# AnalExtend.net
KiCad netlist of a schematic drawn in Altium Designer
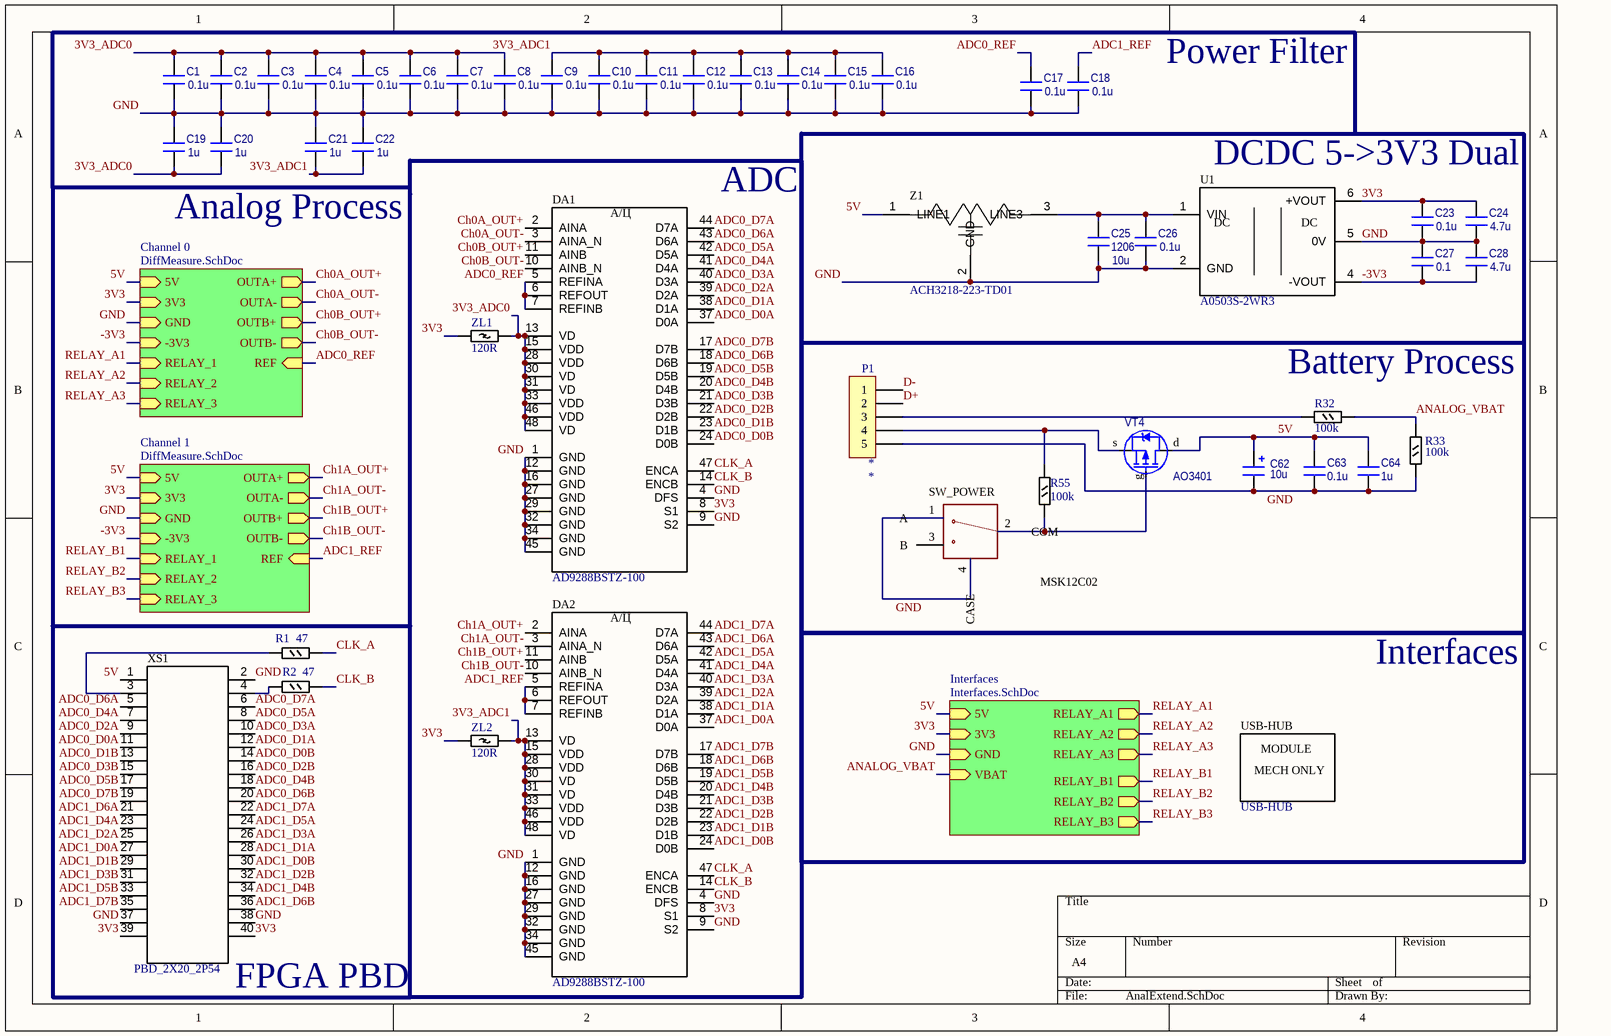
[diagram p0: AnalExtend.SchDoc]

(export (version "E")
  (design (tool "Eeschema 10.0.6"))
  (components
    (comp (ref "C1")
      (value "0.1u")
      (footprint "CAPC2012(0805)N")
      (fields (field (name "PART NUMBER") "CAPC2012(0805)"))
      (libsource (lib "SssAccesDatbase") (part "Capacitor generic"))
    )
    (comp (ref "C2")
      (value "0.1u")
      (footprint "CAPC2012(0805)N")
      (fields (field (name "PART NUMBER") "CAPC2012(0805)"))
      (libsource (lib "SssAccesDatbase") (part "Capacitor generic"))
    )
    (comp (ref "C3")
      (value "0.1u")
      (footprint "CAPC2012(0805)N")
      (fields (field (name "PART NUMBER") "CAPC2012(0805)"))
      (libsource (lib "SssAccesDatbase") (part "Capacitor generic"))
    )
    (comp (ref "C4")
      (value "0.1u")
      (footprint "CAPC2012(0805)N")
      (fields (field (name "PART NUMBER") "CAPC2012(0805)"))
      (libsource (lib "SssAccesDatbase") (part "Capacitor generic"))
    )
    (comp (ref "C5")
      (value "0.1u")
      (footprint "CAPC2012(0805)N")
      (fields (field (name "PART NUMBER") "CAPC2012(0805)"))
      (libsource (lib "SssAccesDatbase") (part "Capacitor generic"))
    )
    (comp (ref "C6")
      (value "0.1u")
      (footprint "CAPC2012(0805)N")
      (fields (field (name "PART NUMBER") "CAPC2012(0805)"))
      (libsource (lib "SssAccesDatbase") (part "Capacitor generic"))
    )
    (comp (ref "C7")
      (value "0.1u")
      (footprint "CAPC2012(0805)N")
      (fields (field (name "PART NUMBER") "CAPC2012(0805)"))
      (libsource (lib "SssAccesDatbase") (part "Capacitor generic"))
    )
    (comp (ref "C8")
      (value "0.1u")
      (footprint "CAPC2012(0805)N")
      (fields (field (name "PART NUMBER") "CAPC2012(0805)"))
      (libsource (lib "SssAccesDatbase") (part "Capacitor generic"))
    )
    (comp (ref "C9")
      (value "0.1u")
      (footprint "CAPC2012(0805)N")
      (fields (field (name "PART NUMBER") "CAPC2012(0805)"))
      (libsource (lib "SssAccesDatbase") (part "Capacitor generic"))
    )
    (comp (ref "C10")
      (value "0.1u")
      (footprint "CAPC2012(0805)N")
      (fields (field (name "PART NUMBER") "CAPC2012(0805)"))
      (libsource (lib "SssAccesDatbase") (part "Capacitor generic"))
    )
    (comp (ref "C11")
      (value "0.1u")
      (footprint "CAPC2012(0805)N")
      (fields (field (name "PART NUMBER") "CAPC2012(0805)"))
      (libsource (lib "SssAccesDatbase") (part "Capacitor generic"))
    )
    (comp (ref "C12")
      (value "0.1u")
      (footprint "CAPC2012(0805)N")
      (fields (field (name "PART NUMBER") "CAPC2012(0805)"))
      (libsource (lib "SssAccesDatbase") (part "Capacitor generic"))
    )
    (comp (ref "C13")
      (value "0.1u")
      (footprint "CAPC2012(0805)N")
      (fields (field (name "PART NUMBER") "CAPC2012(0805)"))
      (libsource (lib "SssAccesDatbase") (part "Capacitor generic"))
    )
    (comp (ref "C14")
      (value "0.1u")
      (footprint "CAPC2012(0805)N")
      (fields (field (name "PART NUMBER") "CAPC2012(0805)"))
      (libsource (lib "SssAccesDatbase") (part "Capacitor generic"))
    )
    (comp (ref "C15")
      (value "0.1u")
      (footprint "CAPC2012(0805)N")
      (fields (field (name "PART NUMBER") "CAPC2012(0805)"))
      (libsource (lib "SssAccesDatbase") (part "Capacitor generic"))
    )
    (comp (ref "C16")
      (value "0.1u")
      (footprint "CAPC2012(0805)N")
      (fields (field (name "PART NUMBER") "CAPC2012(0805)"))
      (libsource (lib "SssAccesDatbase") (part "Capacitor generic"))
    )
    (comp (ref "C17")
      (value "0.1u")
      (footprint "CAPC2012(0805)N")
      (fields (field (name "PART NUMBER") "CAPC2012(0805)"))
      (libsource (lib "SssAccesDatbase") (part "Capacitor generic"))
    )
    (comp (ref "C18")
      (value "0.1u")
      (footprint "CAPC2012(0805)N")
      (fields (field (name "PART NUMBER") "CAPC2012(0805)"))
      (libsource (lib "SssAccesDatbase") (part "Capacitor generic"))
    )
    (comp (ref "C19")
      (value "1u")
      (footprint "CAPC2012(0805)N")
      (fields (field (name "PART NUMBER") "CAPC2012(0805)"))
      (libsource (lib "SssAccesDatbase") (part "Capacitor generic"))
    )
    (comp (ref "C20")
      (value "1u")
      (footprint "CAPC2012(0805)N")
      (fields (field (name "PART NUMBER") "CAPC2012(0805)"))
      (libsource (lib "SssAccesDatbase") (part "Capacitor generic"))
    )
    (comp (ref "C21")
      (value "1u")
      (footprint "CAPC2012(0805)N")
      (fields (field (name "PART NUMBER") "CAPC2012(0805)"))
      (libsource (lib "SssAccesDatbase") (part "Capacitor generic"))
    )
    (comp (ref "C22")
      (value "1u")
      (footprint "CAPC2012(0805)N")
      (fields (field (name "PART NUMBER") "CAPC2012(0805)"))
      (libsource (lib "SssAccesDatbase") (part "Capacitor generic"))
    )
    (comp (ref "C23")
      (value "0.1u")
      (footprint "CAPC2012(0805)N")
      (fields (field (name "PART NUMBER") "CAPC2012(0805)"))
      (libsource (lib "SssAccesDatbase") (part "Capacitor generic"))
    )
    (comp (ref "C24")
      (value "4.7u")
      (footprint "CAPC2012(0805)N")
      (fields (field (name "PART NUMBER") "CAPC2012(0805)"))
      (libsource (lib "SssAccesDatbase") (part "Capacitor generic"))
    )
    (comp (ref "C25")
      (value "10u")
      (footprint "CAP_CER_1206")
      (description "Cap Cer MLCC SMD 50V 2700p C0G NP0 1206 2%")
      (fields
        (field (name "PACKAGE") "1206")
        (field (name "PART NUMBER") "12065A272GAT2A")
        (field (name "MOUSER PART NUMBER") "581-12065A272G")
      )
      (libsource (lib "SssAccesDatbase") (part "Capacitor generic"))
    )
    (comp (ref "C26")
      (value "0.1u")
      (footprint "CAPC2012(0805)N")
      (fields (field (name "PART NUMBER") "CAPC2012(0805)"))
      (libsource (lib "SssAccesDatbase") (part "Capacitor generic"))
    )
    (comp (ref "C27")
      (value "0.1")
      (footprint "CAPC2012(0805)N")
      (fields (field (name "PART NUMBER") "CAPC2012(0805)"))
      (libsource (lib "SssAccesDatbase") (part "Capacitor generic"))
    )
    (comp (ref "C28")
      (value "4.7u")
      (footprint "CAPC2012(0805)N")
      (fields (field (name "PART NUMBER") "CAPC2012(0805)"))
      (libsource (lib "SssAccesDatbase") (part "Capacitor generic"))
    )
    (comp (ref "C62")
      (value "10u")
      (footprint "CAPMP3528X210N")
      (description "Tantalum Capacitors - Solid SMD 35V 1uF 10%")
      (fields (field (name "PART NUMBER") "TAJB105K035SNJ") (field (name "MPN") "581-TAJB105K035S"))
      (libsource (lib "SssAccesDatbase") (part "Capacitor generic polar"))
    )
    (comp (ref "C63")
      (value "0.1u")
      (footprint "CAPC2012(0805)N")
      (fields (field (name "PACKAGE") "0.1u") (field (name "PART NUMBER") "CAPC2012(0805)"))
      (libsource (lib "SssAccesDatbase") (part "Capacitor generic"))
    )
    (comp (ref "C64")
      (value "1u")
      (footprint "CAPC2012(0805)N")
      (fields (field (name "PACKAGE") "1u") (field (name "PART NUMBER") "CAPC2012(0805)"))
      (libsource (lib "SssAccesDatbase") (part "Capacitor generic"))
    )
    (comp (ref "DA1")
      (value "AD9288BSTZ-100")
      (footprint "AD9288BSTZ-100_LQFP48")
      (description "Analog Devices dual 8-bit ADC, 100 MSPS, LQFP-48 ST-48")
      (libsource (lib "Oscill") (part "AD9288BSTZ-100"))
    )
    (comp (ref "DA2")
      (value "AD9288BSTZ-100")
      (footprint "AD9288BSTZ-100_LQFP48")
      (description "Analog Devices dual 8-bit ADC, 100 MSPS, LQFP-48 ST-48")
      (libsource (lib "Oscill") (part "AD9288BSTZ-100"))
    )
    (comp (ref "P1")
      (value "P_HEADER_1x5")
      (footprint "P_HEADER_1x5_2.54_ANGLE")
      (description "Pin Header")
      (fields (field (name "SCH_FOOTPRINT") "*") (field (name "ALTIUM_VALUE") "*"))
      (libsource (lib "P_HEADER_1x5") (part "P_HEADER_1x5"))
    )
    (comp (ref "R1")
      (value "47")
      (footprint "RESC2012(0805)N")
      (fields (field (name "PART NUMBER") "RESC2012(0805)"))
      (libsource (lib "SssAccesDatbase") (part "Resistor 0,125W"))
    )
    (comp (ref "R2")
      (value "47")
      (footprint "RESC2012(0805)N")
      (fields (field (name "PART NUMBER") "RESC2012(0805)"))
      (libsource (lib "SssAccesDatbase") (part "Resistor 0,125W"))
    )
    (comp (ref "R32")
      (value "100k")
      (footprint "RESC2012(0805)N")
      (fields (field (name "PART NUMBER") "RESC2012(0805)"))
      (libsource (lib "SssAccesDatbase") (part "Resistor 0,125W"))
    )
    (comp (ref "R33")
      (value "100k")
      (footprint "RESC2012(0805)N")
      (fields (field (name "PART NUMBER") "RESC2012(0805)"))
      (libsource (lib "") (part "Resistor 0,125W_2"))
    )
    (comp (ref "R55")
      (value "100k")
      (footprint "RESC2012(0805)N")
      (fields (field (name "PART NUMBER") "RESC2012(0805)"))
      (libsource (lib "") (part "Resistor 0,125W_1"))
    )
    (comp (ref "SW_POWER")
      (value "MSK12C02")
      (footprint "MSK12C02")
      (description "Shou Han MSK12C02 miniature SMD SPDT slide switch, ON-ON, 12 VDC 50 mA; four case tabs are pin 4")
      (fields (field (name "MANUFACTURER") "SHOU HAN") (field (name "LCSC PART NUMBER") "C431540"))
      (libsource (lib "MSK12C02") (part "MSK12C02"))
    )
    (comp (ref "U1")
      (value "A0503S-2WR3")
      (footprint "A0503S-2WR3_SIP5")
      (description "YLPTEC 2 W isolated DC/DC, 5 V input, +/-3.3 V dual output")
      (libsource (lib "Oscill") (part "A0503S-2WR3"))
    )
    (comp (ref "USB-HUB")
      (value "USB-HUB")
      (footprint "Oscill:MINGWU_29P3X18P9_MECH")
      (description "Mechanical-only Mingwudianzi module; no electrical pins")
      (libsource (lib "Oscill") (part "MINGWU_29P3X18P9_MECH"))
    )
    (comp (ref "VT4")
      (value "AO3401")
      (footprint "SOT23-3N")
      (description "MOSFET 30V P-Channel Enhancement Mode MOSFET-ESD Protected")
      (fields
        (field (name "PART NUMBER") "PJA3433_R1_00001")
        (field (name "DIGI-KEY PART NUMBER") "3757-PJA3433_R1_00001CT-ND")
      )
      (libsource (lib "SssAccesDatbase") (part "TRANS-P-Channel-GSD"))
    )
    (comp (ref "XS1")
      (value "PBD_2X20_2P54")
      (footprint "PBD_2X20_2P54_THT")
      (description "PBD-40 vertical 2x20 2.54 mm female through-hole socket")
      (libsource (lib "Oscill") (part "PBD_2X20_2P54"))
    )
    (comp (ref "Z1")
      (value "ACH3218-223-TD01")
      (footprint "ACH3218_3TERM_FILTER")
      (description "TDK 22 nF three-terminal T-type EMI filter, 20 V, 1.5 A")
      (libsource (lib "Oscill") (part "ACH3218-223-TD01"))
    )
    (comp (ref "ZL1")
      (value "120R")
      (footprint "INDC1608(0603)N")
      (description "ferite bead")
      (fields
        (field (name "PART NUMBER") "Ferite1608(0603)")
        (field (name "MANUFACTURER PART NUMBER") "BLM15PX471SN1D")
      )
      (libsource (lib "SssAccesDatbase") (part "ZL"))
    )
    (comp (ref "ZL2")
      (value "120R")
      (footprint "INDC1608(0603)N")
      (description "ferite bead")
      (fields
        (field (name "PART NUMBER") "Ferite1608(0603)")
        (field (name "MANUFACTURER PART NUMBER") "BLM15PX471SN1D")
      )
      (libsource (lib "SssAccesDatbase") (part "ZL"))
    )
  )
  (nets
    (net (code "1") (name "/-3V3") (class "Default")
      (node (ref "C27") (pin "2") (pinfunction "2_2") (pintype "passive"))
      (node (ref "C28") (pin "2") (pinfunction "2_2") (pintype "passive"))
      (node (ref "U1") (pin "4") (pinfunction "-VOUT_4") (pintype "passive"))
    )
    (net (code "2") (name "/3V3") (class "Default")
      (node (ref "C23") (pin "1") (pinfunction "1_1") (pintype "passive"))
      (node (ref "C24") (pin "1") (pinfunction "1_1") (pintype "passive"))
      (node (ref "DA1") (pin "8") (pinfunction "S1_8") (pintype "passive"))
      (node (ref "DA2") (pin "8") (pinfunction "S1_8") (pintype "passive"))
      (node (ref "U1") (pin "6") (pinfunction "+VOUT_6") (pintype "passive"))
      (node (ref "XS1") (pin "39") (pintype "passive"))
      (node (ref "XS1") (pin "40") (pintype "passive"))
      (node (ref "ZL1") (pin "1") (pinfunction "1_1") (pintype "passive"))
      (node (ref "ZL2") (pin "1") (pinfunction "1_1") (pintype "passive"))
    )
    (net (code "3") (name "/3V3_ADC0") (class "Default")
      (node (ref "C1") (pin "1") (pinfunction "1_1") (pintype "passive"))
      (node (ref "C19") (pin "2") (pinfunction "2_2") (pintype "passive"))
      (node (ref "C2") (pin "1") (pinfunction "1_1") (pintype "passive"))
      (node (ref "C20") (pin "2") (pinfunction "2_2") (pintype "passive"))
      (node (ref "C3") (pin "1") (pinfunction "1_1") (pintype "passive"))
      (node (ref "C4") (pin "1") (pinfunction "1_1") (pintype "passive"))
      (node (ref "C5") (pin "1") (pinfunction "1_1") (pintype "passive"))
      (node (ref "C6") (pin "1") (pinfunction "1_1") (pintype "passive"))
      (node (ref "C7") (pin "1") (pinfunction "1_1") (pintype "passive"))
      (node (ref "C8") (pin "1") (pinfunction "1_1") (pintype "passive"))
      (node (ref "DA1") (pin "13") (pinfunction "VD_13") (pintype "passive"))
      (node (ref "DA1") (pin "15") (pinfunction "VDD_15") (pintype "passive"))
      (node (ref "DA1") (pin "28") (pinfunction "VDD_28") (pintype "passive"))
      (node (ref "DA1") (pin "30") (pinfunction "VD_30") (pintype "passive"))
      (node (ref "DA1") (pin "31") (pinfunction "VD_31") (pintype "passive"))
      (node (ref "DA1") (pin "33") (pinfunction "VDD_33") (pintype "passive"))
      (node (ref "DA1") (pin "46") (pinfunction "VDD_46") (pintype "passive"))
      (node (ref "DA1") (pin "48") (pinfunction "VD_48") (pintype "passive"))
      (node (ref "ZL1") (pin "2") (pinfunction "2_2") (pintype "passive"))
    )
    (net (code "4") (name "/3V3_ADC1") (class "Default")
      (node (ref "C10") (pin "1") (pinfunction "1_1") (pintype "passive"))
      (node (ref "C11") (pin "1") (pinfunction "1_1") (pintype "passive"))
      (node (ref "C12") (pin "1") (pinfunction "1_1") (pintype "passive"))
      (node (ref "C13") (pin "1") (pinfunction "1_1") (pintype "passive"))
      (node (ref "C14") (pin "1") (pinfunction "1_1") (pintype "passive"))
      (node (ref "C15") (pin "1") (pinfunction "1_1") (pintype "passive"))
      (node (ref "C16") (pin "1") (pinfunction "1_1") (pintype "passive"))
      (node (ref "C21") (pin "2") (pinfunction "2_2") (pintype "passive"))
      (node (ref "C22") (pin "2") (pinfunction "2_2") (pintype "passive"))
      (node (ref "C9") (pin "1") (pinfunction "1_1") (pintype "passive"))
      (node (ref "DA2") (pin "13") (pinfunction "VD_13") (pintype "passive"))
      (node (ref "DA2") (pin "15") (pinfunction "VDD_15") (pintype "passive"))
      (node (ref "DA2") (pin "28") (pinfunction "VDD_28") (pintype "passive"))
      (node (ref "DA2") (pin "30") (pinfunction "VD_30") (pintype "passive"))
      (node (ref "DA2") (pin "31") (pinfunction "VD_31") (pintype "passive"))
      (node (ref "DA2") (pin "33") (pinfunction "VDD_33") (pintype "passive"))
      (node (ref "DA2") (pin "46") (pinfunction "VDD_46") (pintype "passive"))
      (node (ref "DA2") (pin "48") (pinfunction "VD_48") (pintype "passive"))
      (node (ref "ZL2") (pin "2") (pinfunction "2_2") (pintype "passive"))
    )
    (net (code "5") (name "/5V") (class "Default")
      (node (ref "C62") (pin "1") (pinfunction "1_1") (pintype "passive"))
      (node (ref "C63") (pin "1") (pinfunction "1_1") (pintype "passive"))
      (node (ref "C64") (pin "1") (pinfunction "1_1") (pintype "passive"))
      (node (ref "VT4") (pin "d") (pinfunction "d_d") (pintype "passive"))
      (node (ref "XS1") (pin "1") (pintype "passive"))
      (node (ref "Z1") (pin "1") (pinfunction "LINE1_1") (pintype "passive"))
    )
    (net (code "6") (name "/ADC0_D0A") (class "Default")
      (node (ref "DA1") (pin "37") (pinfunction "D0A_37") (pintype "passive"))
      (node (ref "XS1") (pin "11") (pintype "passive"))
    )
    (net (code "7") (name "/ADC0_D0B") (class "Default")
      (node (ref "DA1") (pin "24") (pinfunction "D0B_24") (pintype "passive"))
      (node (ref "XS1") (pin "14") (pintype "passive"))
    )
    (net (code "8") (name "/ADC0_D1A") (class "Default")
      (node (ref "DA1") (pin "38") (pinfunction "D1A_38") (pintype "passive"))
      (node (ref "XS1") (pin "12") (pintype "passive"))
    )
    (net (code "9") (name "/ADC0_D1B") (class "Default")
      (node (ref "DA1") (pin "23") (pinfunction "D1B_23") (pintype "passive"))
      (node (ref "XS1") (pin "13") (pintype "passive"))
    )
    (net (code "10") (name "/ADC0_D2A") (class "Default")
      (node (ref "DA1") (pin "39") (pinfunction "D2A_39") (pintype "passive"))
      (node (ref "XS1") (pin "9") (pintype "passive"))
    )
    (net (code "11") (name "/ADC0_D2B") (class "Default")
      (node (ref "DA1") (pin "22") (pinfunction "D2B_22") (pintype "passive"))
      (node (ref "XS1") (pin "16") (pintype "passive"))
    )
    (net (code "12") (name "/ADC0_D3A") (class "Default")
      (node (ref "DA1") (pin "40") (pinfunction "D3A_40") (pintype "passive"))
      (node (ref "XS1") (pin "10") (pintype "passive"))
    )
    (net (code "13") (name "/ADC0_D3B") (class "Default")
      (node (ref "DA1") (pin "21") (pinfunction "D3B_21") (pintype "passive"))
      (node (ref "XS1") (pin "15") (pintype "passive"))
    )
    (net (code "14") (name "/ADC0_D4A") (class "Default")
      (node (ref "DA1") (pin "41") (pinfunction "D4A_41") (pintype "passive"))
      (node (ref "XS1") (pin "7") (pintype "passive"))
    )
    (net (code "15") (name "/ADC0_D4B") (class "Default")
      (node (ref "DA1") (pin "20") (pinfunction "D4B_20") (pintype "passive"))
      (node (ref "XS1") (pin "18") (pintype "passive"))
    )
    (net (code "16") (name "/ADC0_D5A") (class "Default")
      (node (ref "DA1") (pin "42") (pinfunction "D5A_42") (pintype "passive"))
      (node (ref "XS1") (pin "8") (pintype "passive"))
    )
    (net (code "17") (name "/ADC0_D5B") (class "Default")
      (node (ref "DA1") (pin "19") (pinfunction "D5B_19") (pintype "passive"))
      (node (ref "XS1") (pin "17") (pintype "passive"))
    )
    (net (code "18") (name "/ADC0_D6A") (class "Default")
      (node (ref "DA1") (pin "43") (pinfunction "D6A_43") (pintype "passive"))
      (node (ref "XS1") (pin "5") (pintype "passive"))
    )
    (net (code "19") (name "/ADC0_D6B") (class "Default")
      (node (ref "DA1") (pin "18") (pinfunction "D6B_18") (pintype "passive"))
      (node (ref "XS1") (pin "20") (pintype "passive"))
    )
    (net (code "20") (name "/ADC0_D7A") (class "Default")
      (node (ref "DA1") (pin "44") (pinfunction "D7A_44") (pintype "passive"))
      (node (ref "XS1") (pin "6") (pintype "passive"))
    )
    (net (code "21") (name "/ADC0_D7B") (class "Default")
      (node (ref "DA1") (pin "17") (pinfunction "D7B_17") (pintype "passive"))
      (node (ref "XS1") (pin "19") (pintype "passive"))
    )
    (net (code "22") (name "/ADC0_REF") (class "Default")
      (node (ref "C17") (pin "1") (pinfunction "1_1") (pintype "passive"))
      (node (ref "DA1") (pin "5") (pinfunction "REFINA_5") (pintype "passive"))
      (node (ref "DA1") (pin "6") (pinfunction "REFOUT_6") (pintype "passive"))
      (node (ref "DA1") (pin "7") (pinfunction "REFINB_7") (pintype "passive"))
    )
    (net (code "23") (name "/ADC1_D0A") (class "Default")
      (node (ref "DA2") (pin "37") (pinfunction "D0A_37") (pintype "passive"))
      (node (ref "XS1") (pin "27") (pintype "passive"))
    )
    (net (code "24") (name "/ADC1_D0B") (class "Default")
      (node (ref "DA2") (pin "24") (pinfunction "D0B_24") (pintype "passive"))
      (node (ref "XS1") (pin "30") (pintype "passive"))
    )
    (net (code "25") (name "/ADC1_D1A") (class "Default")
      (node (ref "DA2") (pin "38") (pinfunction "D1A_38") (pintype "passive"))
      (node (ref "XS1") (pin "28") (pintype "passive"))
    )
    (net (code "26") (name "/ADC1_D1B") (class "Default")
      (node (ref "DA2") (pin "23") (pinfunction "D1B_23") (pintype "passive"))
      (node (ref "XS1") (pin "29") (pintype "passive"))
    )
    (net (code "27") (name "/ADC1_D2A") (class "Default")
      (node (ref "DA2") (pin "39") (pinfunction "D2A_39") (pintype "passive"))
      (node (ref "XS1") (pin "25") (pintype "passive"))
    )
    (net (code "28") (name "/ADC1_D2B") (class "Default")
      (node (ref "DA2") (pin "22") (pinfunction "D2B_22") (pintype "passive"))
      (node (ref "XS1") (pin "32") (pintype "passive"))
    )
    (net (code "29") (name "/ADC1_D3A") (class "Default")
      (node (ref "DA2") (pin "40") (pinfunction "D3A_40") (pintype "passive"))
      (node (ref "XS1") (pin "26") (pintype "passive"))
    )
    (net (code "30") (name "/ADC1_D3B") (class "Default")
      (node (ref "DA2") (pin "21") (pinfunction "D3B_21") (pintype "passive"))
      (node (ref "XS1") (pin "31") (pintype "passive"))
    )
    (net (code "31") (name "/ADC1_D4A") (class "Default")
      (node (ref "DA2") (pin "41") (pinfunction "D4A_41") (pintype "passive"))
      (node (ref "XS1") (pin "23") (pintype "passive"))
    )
    (net (code "32") (name "/ADC1_D4B") (class "Default")
      (node (ref "DA2") (pin "20") (pinfunction "D4B_20") (pintype "passive"))
      (node (ref "XS1") (pin "34") (pintype "passive"))
    )
    (net (code "33") (name "/ADC1_D5A") (class "Default")
      (node (ref "DA2") (pin "42") (pinfunction "D5A_42") (pintype "passive"))
      (node (ref "XS1") (pin "24") (pintype "passive"))
    )
    (net (code "34") (name "/ADC1_D5B") (class "Default")
      (node (ref "DA2") (pin "19") (pinfunction "D5B_19") (pintype "passive"))
      (node (ref "XS1") (pin "33") (pintype "passive"))
    )
    (net (code "35") (name "/ADC1_D6A") (class "Default")
      (node (ref "DA2") (pin "43") (pinfunction "D6A_43") (pintype "passive"))
      (node (ref "XS1") (pin "21") (pintype "passive"))
    )
    (net (code "36") (name "/ADC1_D6B") (class "Default")
      (node (ref "DA2") (pin "18") (pinfunction "D6B_18") (pintype "passive"))
      (node (ref "XS1") (pin "36") (pintype "passive"))
    )
    (net (code "37") (name "/ADC1_D7A") (class "Default")
      (node (ref "DA2") (pin "44") (pinfunction "D7A_44") (pintype "passive"))
      (node (ref "XS1") (pin "22") (pintype "passive"))
    )
    (net (code "38") (name "/ADC1_D7B") (class "Default")
      (node (ref "DA2") (pin "17") (pinfunction "D7B_17") (pintype "passive"))
      (node (ref "XS1") (pin "35") (pintype "passive"))
    )
    (net (code "39") (name "/ADC1_REF") (class "Default")
      (node (ref "C18") (pin "1") (pinfunction "1_1") (pintype "passive"))
      (node (ref "DA2") (pin "5") (pinfunction "REFINA_5") (pintype "passive"))
      (node (ref "DA2") (pin "6") (pinfunction "REFOUT_6") (pintype "passive"))
      (node (ref "DA2") (pin "7") (pinfunction "REFINB_7") (pintype "passive"))
    )
    (net (code "40") (name "/ANALOG_VBAT") (class "Default")
      (node (ref "R32") (pin "2") (pinfunction "2_2") (pintype "passive"))
      (node (ref "R33") (pin "1") (pinfunction "1_1") (pintype "passive"))
    )
    (net (code "41") (name "/CLK_A") (class "Default")
      (node (ref "DA1") (pin "47") (pinfunction "ENCA_47") (pintype "passive"))
      (node (ref "DA2") (pin "47") (pinfunction "ENCA_47") (pintype "passive"))
      (node (ref "R1") (pin "2") (pinfunction "2_2") (pintype "passive"))
    )
    (net (code "42") (name "/CLK_B") (class "Default")
      (node (ref "DA1") (pin "14") (pinfunction "ENCB_14") (pintype "passive"))
      (node (ref "DA2") (pin "14") (pinfunction "ENCB_14") (pintype "passive"))
      (node (ref "R2") (pin "2") (pinfunction "2_2") (pintype "passive"))
    )
    (net (code "43") (name "/Ch0A_OUT+") (class "Default")
      (node (ref "DA1") (pin "2") (pinfunction "AINA_2") (pintype "passive"))
    )
    (net (code "44") (name "/Ch0A_OUT-") (class "Default")
      (node (ref "DA1") (pin "3") (pinfunction "AINA_N_3") (pintype "passive"))
    )
    (net (code "45") (name "/Ch0B_OUT+") (class "Default")
      (node (ref "DA1") (pin "11") (pinfunction "AINB_11") (pintype "passive"))
    )
    (net (code "46") (name "/Ch0B_OUT-") (class "Default")
      (node (ref "DA1") (pin "10") (pinfunction "AINB_N_10") (pintype "passive"))
    )
    (net (code "47") (name "/Ch1A_OUT+") (class "Default")
      (node (ref "DA2") (pin "2") (pinfunction "AINA_2") (pintype "passive"))
    )
    (net (code "48") (name "/Ch1A_OUT-") (class "Default")
      (node (ref "DA2") (pin "3") (pinfunction "AINA_N_3") (pintype "passive"))
    )
    (net (code "49") (name "/Ch1B_OUT+") (class "Default")
      (node (ref "DA2") (pin "11") (pinfunction "AINB_11") (pintype "passive"))
    )
    (net (code "50") (name "/Ch1B_OUT-") (class "Default")
      (node (ref "DA2") (pin "10") (pinfunction "AINB_N_10") (pintype "passive"))
    )
    (net (code "51") (name "/D+") (class "Default")
      (node (ref "P1") (pin "2") (pinfunction "2_2") (pintype "passive"))
    )
    (net (code "52") (name "/D-") (class "Default")
      (node (ref "P1") (pin "1") (pinfunction "1_1") (pintype "passive"))
    )
    (net (code "53") (name "/GND") (class "Default")
      (node (ref "C1") (pin "2") (pinfunction "2_2") (pintype "passive"))
      (node (ref "C10") (pin "2") (pinfunction "2_2") (pintype "passive"))
      (node (ref "C11") (pin "2") (pinfunction "2_2") (pintype "passive"))
      (node (ref "C12") (pin "2") (pinfunction "2_2") (pintype "passive"))
      (node (ref "C13") (pin "2") (pinfunction "2_2") (pintype "passive"))
      (node (ref "C14") (pin "2") (pinfunction "2_2") (pintype "passive"))
      (node (ref "C15") (pin "2") (pinfunction "2_2") (pintype "passive"))
      (node (ref "C16") (pin "2") (pinfunction "2_2") (pintype "passive"))
      (node (ref "C17") (pin "2") (pinfunction "2_2") (pintype "passive"))
      (node (ref "C18") (pin "2") (pinfunction "2_2") (pintype "passive"))
      (node (ref "C19") (pin "1") (pinfunction "1_1") (pintype "passive"))
      (node (ref "C2") (pin "2") (pinfunction "2_2") (pintype "passive"))
      (node (ref "C20") (pin "1") (pinfunction "1_1") (pintype "passive"))
      (node (ref "C21") (pin "1") (pinfunction "1_1") (pintype "passive"))
      (node (ref "C22") (pin "1") (pinfunction "1_1") (pintype "passive"))
      (node (ref "C23") (pin "2") (pinfunction "2_2") (pintype "passive"))
      (node (ref "C24") (pin "2") (pinfunction "2_2") (pintype "passive"))
      (node (ref "C25") (pin "2") (pinfunction "2_2") (pintype "passive"))
      (node (ref "C26") (pin "2") (pinfunction "2_2") (pintype "passive"))
      (node (ref "C27") (pin "1") (pinfunction "1_1") (pintype "passive"))
      (node (ref "C28") (pin "1") (pinfunction "1_1") (pintype "passive"))
      (node (ref "C3") (pin "2") (pinfunction "2_2") (pintype "passive"))
      (node (ref "C4") (pin "2") (pinfunction "2_2") (pintype "passive"))
      (node (ref "C5") (pin "2") (pinfunction "2_2") (pintype "passive"))
      (node (ref "C6") (pin "2") (pinfunction "2_2") (pintype "passive"))
      (node (ref "C62") (pin "2") (pinfunction "2_2") (pintype "passive"))
      (node (ref "C63") (pin "2") (pinfunction "2_2") (pintype "passive"))
      (node (ref "C64") (pin "2") (pinfunction "2_2") (pintype "passive"))
      (node (ref "C7") (pin "2") (pinfunction "2_2") (pintype "passive"))
      (node (ref "C8") (pin "2") (pinfunction "2_2") (pintype "passive"))
      (node (ref "C9") (pin "2") (pinfunction "2_2") (pintype "passive"))
      (node (ref "DA1") (pin "1") (pinfunction "GND_1") (pintype "passive"))
      (node (ref "DA1") (pin "12") (pinfunction "GND_12") (pintype "passive"))
      (node (ref "DA1") (pin "16") (pinfunction "GND_16") (pintype "passive"))
      (node (ref "DA1") (pin "27") (pinfunction "GND_27") (pintype "passive"))
      (node (ref "DA1") (pin "29") (pinfunction "GND_29") (pintype "passive"))
      (node (ref "DA1") (pin "32") (pinfunction "GND_32") (pintype "passive"))
      (node (ref "DA1") (pin "34") (pinfunction "GND_34") (pintype "passive"))
      (node (ref "DA1") (pin "4") (pinfunction "DFS_4") (pintype "passive"))
      (node (ref "DA1") (pin "45") (pinfunction "GND_45") (pintype "passive"))
      (node (ref "DA1") (pin "9") (pinfunction "S2_9") (pintype "passive"))
      (node (ref "DA2") (pin "1") (pinfunction "GND_1") (pintype "passive"))
      (node (ref "DA2") (pin "12") (pinfunction "GND_12") (pintype "passive"))
      (node (ref "DA2") (pin "16") (pinfunction "GND_16") (pintype "passive"))
      (node (ref "DA2") (pin "27") (pinfunction "GND_27") (pintype "passive"))
      (node (ref "DA2") (pin "29") (pinfunction "GND_29") (pintype "passive"))
      (node (ref "DA2") (pin "32") (pinfunction "GND_32") (pintype "passive"))
      (node (ref "DA2") (pin "34") (pinfunction "GND_34") (pintype "passive"))
      (node (ref "DA2") (pin "4") (pinfunction "DFS_4") (pintype "passive"))
      (node (ref "DA2") (pin "45") (pinfunction "GND_45") (pintype "passive"))
      (node (ref "DA2") (pin "9") (pinfunction "S2_9") (pintype "passive"))
      (node (ref "P1") (pin "5") (pinfunction "5_5") (pintype "passive"))
      (node (ref "R33") (pin "2") (pinfunction "2_2") (pintype "passive"))
      (node (ref "SW_POWER") (pin "1") (pinfunction "A_1") (pintype "passive"))
      (node (ref "SW_POWER") (pin "4") (pinfunction "CASE_4") (pintype "passive"))
      (node (ref "U1") (pin "2") (pinfunction "GND_2") (pintype "passive"))
      (node (ref "U1") (pin "5") (pinfunction "0V_5") (pintype "passive"))
      (node (ref "XS1") (pin "2") (pintype "passive"))
      (node (ref "XS1") (pin "37") (pintype "passive"))
      (node (ref "XS1") (pin "38") (pintype "passive"))
      (node (ref "Z1") (pin "2") (pinfunction "GND_2") (pintype "passive"))
    )
    (net (code "60") (name "Net-(P1-Pad3)") (class "Default")
      (node (ref "P1") (pin "3") (pinfunction "3_3") (pintype "passive"))
      (node (ref "R32") (pin "1") (pinfunction "1_1") (pintype "passive"))
    )
    (net (code "61") (name "Net-(P1-Pad4)") (class "Default")
      (node (ref "P1") (pin "4") (pinfunction "4_4") (pintype "passive"))
      (node (ref "R55") (pin "2") (pinfunction "2_2") (pintype "passive"))
      (node (ref "VT4") (pin "s") (pinfunction "s_s") (pintype "passive"))
    )
    (net (code "62") (name "Net-(R1-Pad1)") (class "Default")
      (node (ref "R1") (pin "1") (pinfunction "1_1") (pintype "passive"))
      (node (ref "XS1") (pin "3") (pintype "passive"))
    )
    (net (code "63") (name "Net-(R2-Pad1)") (class "Default")
      (node (ref "R2") (pin "1") (pinfunction "1_1") (pintype "passive"))
      (node (ref "XS1") (pin "4") (pintype "passive"))
    )
    (net (code "64") (name "Net-(SW_POWER-COM)") (class "Default")
      (node (ref "R55") (pin "1") (pinfunction "1_1") (pintype "passive"))
      (node (ref "SW_POWER") (pin "2") (pinfunction "COM_2") (pintype "passive"))
      (node (ref "VT4") (pin "g") (pinfunction "g_g") (pintype "passive"))
    )
    (net (code "65") (name "Net-(U1-VIN)") (class "Default")
      (node (ref "C25") (pin "1") (pinfunction "1_1") (pintype "passive"))
      (node (ref "C26") (pin "1") (pinfunction "1_1") (pintype "passive"))
      (node (ref "U1") (pin "1") (pinfunction "VIN_1") (pintype "passive"))
      (node (ref "Z1") (pin "3") (pinfunction "LINE3_3") (pintype "passive"))
    )
    (net (code "66") (name "unconnected-(SW_POWER-B-Pad3)") (class "Default")
      (node (ref "SW_POWER") (pin "3") (pinfunction "B_3") (pintype "passive"))
    )
  )
)
